# OSO-SCAP-B1-01.net
KiCad netlist of a schematic drawn in EAGLE
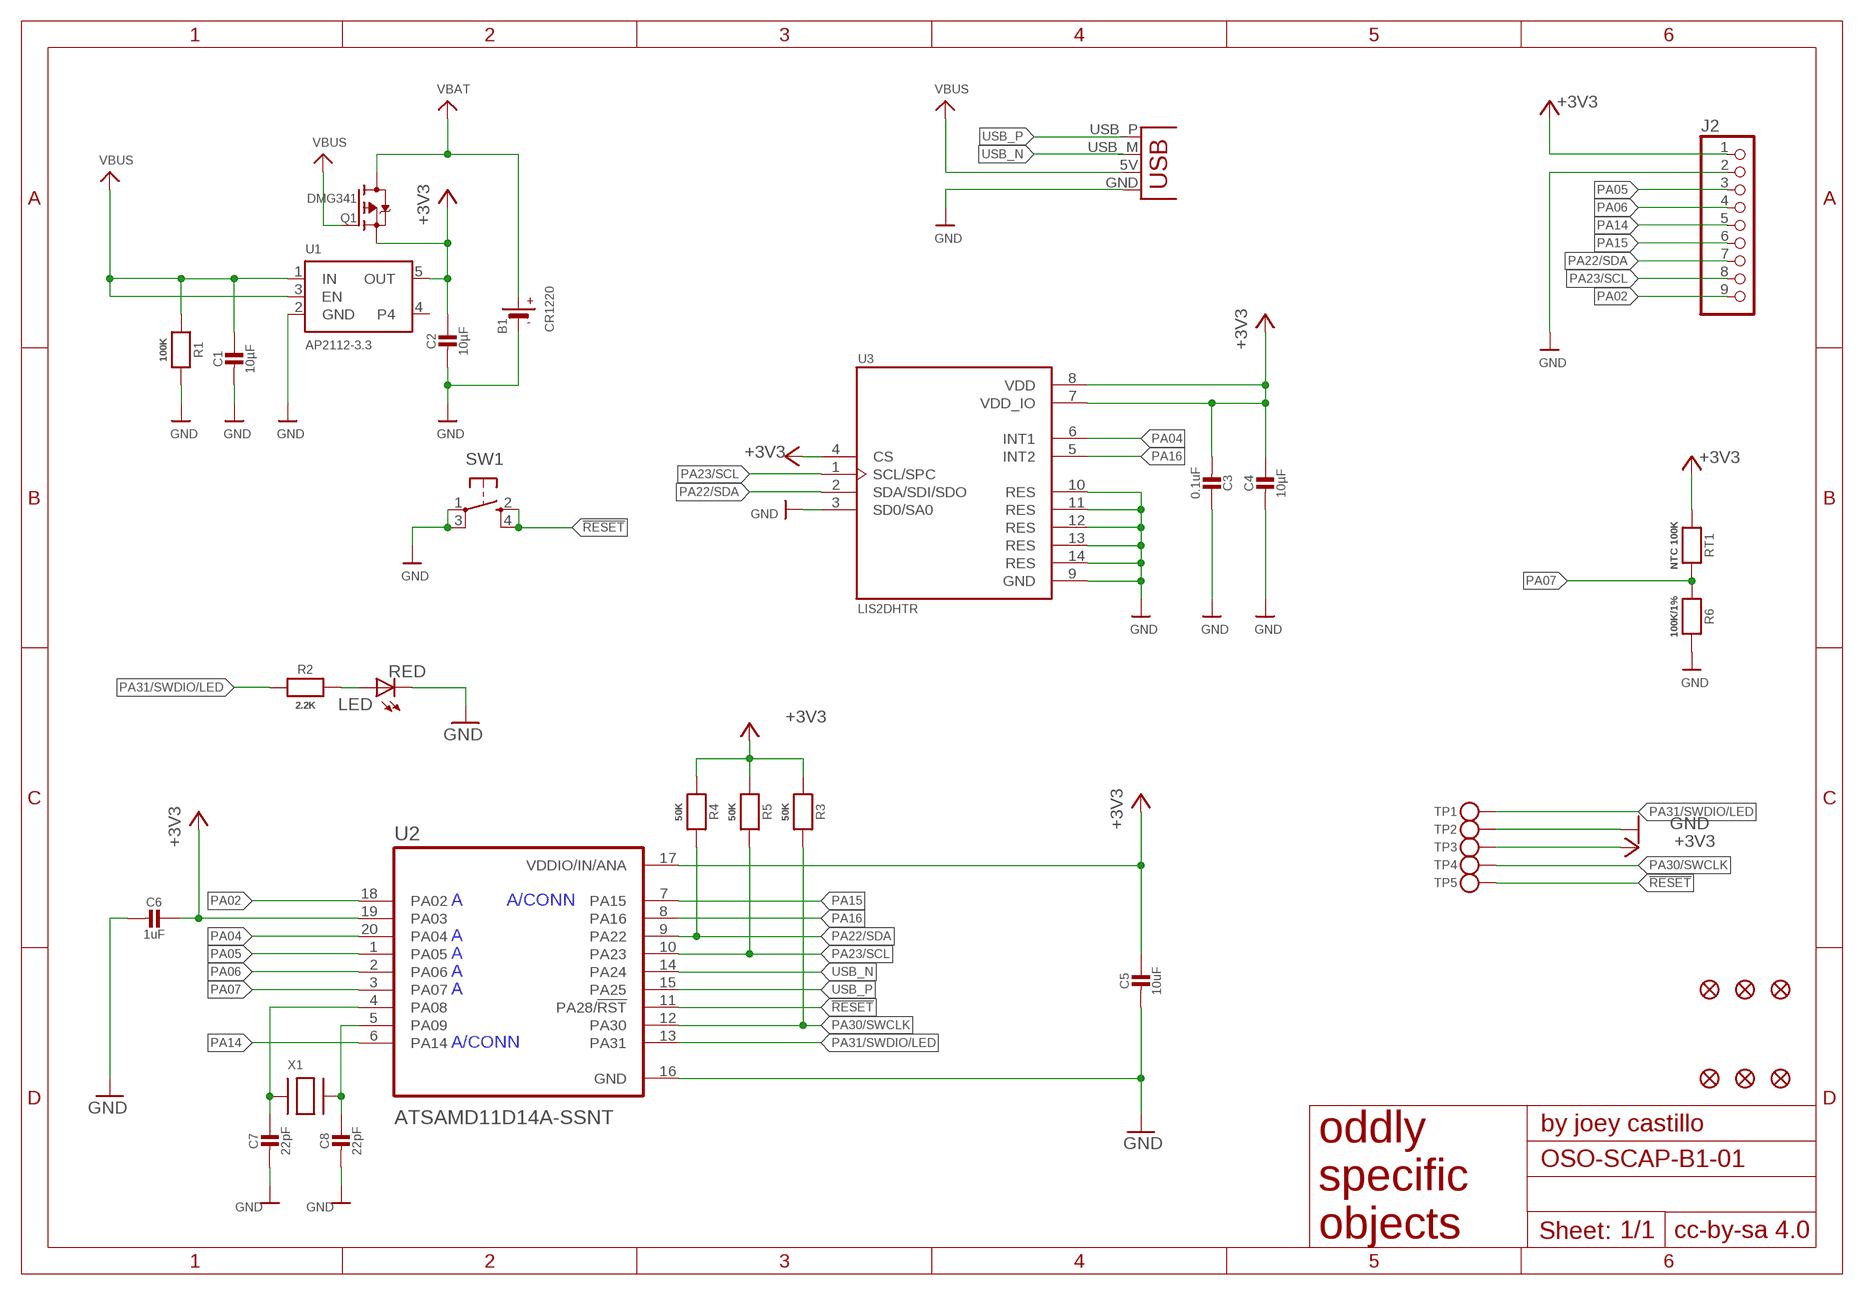
[diagram p0: schematic, sheet 1]

(export (version "E")
  (design (tool "Eeschema 10.0.6"))
  (components
    (comp (ref "B1")
      (value "CR1220")
      (footprint "eagle-import:CR1220")
      (libsource (lib "eagle-import") (part "BATTERYCR1220_SMT"))
    )
    (comp (ref "C1")
      (value "10µF")
      (footprint "eagle-import:0805-NO")
      (libsource (lib "eagle-import") (part "CAP_CERAMIC0805-NOOUTLINE"))
    )
    (comp (ref "C2")
      (value "10µF")
      (footprint "eagle-import:0805-NO")
      (libsource (lib "eagle-import") (part "CAP_CERAMIC0805-NOOUTLINE"))
    )
    (comp (ref "C3")
      (value "0.1uF")
      (footprint "eagle-import:0805-NO")
      (libsource (lib "eagle-import") (part "CAP_CERAMIC0805-NOOUTLINE"))
    )
    (comp (ref "C4")
      (value "10µF")
      (footprint "eagle-import:0805-NO")
      (libsource (lib "eagle-import") (part "CAP_CERAMIC0805-NOOUTLINE"))
    )
    (comp (ref "C5")
      (value "10uF")
      (footprint "eagle-import:0805-NO")
      (libsource (lib "eagle-import") (part "CAP_CERAMIC0805-NOOUTLINE"))
    )
    (comp (ref "C6")
      (value "1uF")
      (footprint "eagle-import:0805-NO")
      (libsource (lib "eagle-import") (part "CAP_CERAMIC0805-NOOUTLINE"))
    )
    (comp (ref "C7")
      (value "22pF")
      (footprint "eagle-import:0805-NO")
      (libsource (lib "eagle-import") (part "CAP_CERAMIC0805-NOOUTLINE"))
    )
    (comp (ref "C8")
      (value "22pF")
      (footprint "eagle-import:0805-NO")
      (libsource (lib "eagle-import") (part "CAP_CERAMIC0805-NOOUTLINE"))
    )
    (comp (ref "FID1")
      (value "FIDUCIAL_1MM")
      (footprint "eagle-import:FIDUCIAL_1MM")
      (libsource (lib "eagle-import") (part "FIDUCIAL_1MM"))
    )
    (comp (ref "FID2")
      (value "FIDUCIAL_1MM")
      (footprint "eagle-import:FIDUCIAL_1MM")
      (libsource (lib "eagle-import") (part "FIDUCIAL_1MM"))
    )
    (comp (ref "FID3")
      (value "FIDUCIAL_1MM")
      (footprint "eagle-import:FIDUCIAL_1MM")
      (libsource (lib "eagle-import") (part "FIDUCIAL_1MM"))
    )
    (comp (ref "FID4")
      (value "FIDUCIAL_1MM")
      (footprint "eagle-import:FIDUCIAL_1MM")
      (libsource (lib "eagle-import") (part "FIDUCIAL_1MM"))
    )
    (comp (ref "FID5")
      (value "FIDUCIAL_1MM")
      (footprint "eagle-import:FIDUCIAL_1MM")
      (libsource (lib "eagle-import") (part "FIDUCIAL_1MM"))
    )
    (comp (ref "FID6")
      (value "FIDUCIAL_1MM")
      (footprint "eagle-import:FIDUCIAL_1MM")
      (libsource (lib "eagle-import") (part "FIDUCIAL_1MM"))
    )
    (comp (ref "J1")
      (value "USBPCB")
      (footprint "eagle-import:USB-A-PCB")
      (libsource (lib "eagle-import") (part "USBPCB"))
    )
    (comp (ref "J2")
      (value "HEADER-1X9_JSTSH")
      (footprint "eagle-import:JST_SH9")
      (libsource (lib "eagle-import") (part "HEADER-1X9_JSTSH"))
    )
    (comp (ref "LED")
      (value "RED")
      (footprint "eagle-import:CHIP-LED0805")
      (libsource (lib "eagle-import") (part "LEDCHIP-LED0805"))
    )
    (comp (ref "Q1")
      (value "DMG341")
      (footprint "eagle-import:SOT23-R")
      (libsource (lib "eagle-import") (part "MOSFET-P"))
    )
    (comp (ref "R1")
      (value "100K")
      (footprint "eagle-import:0805-NO")
      (libsource (lib "eagle-import") (part "RESISTOR0805_NOOUTLINE"))
    )
    (comp (ref "R2")
      (value "2.2K")
      (footprint "eagle-import:0805-NO")
      (libsource (lib "eagle-import") (part "RESISTOR0805_NOOUTLINE"))
    )
    (comp (ref "R3")
      (value "50K")
      (footprint "eagle-import:0805-NO")
      (libsource (lib "eagle-import") (part "RESISTOR0805_NOOUTLINE"))
    )
    (comp (ref "R4")
      (value "50K")
      (footprint "eagle-import:0805-NO")
      (libsource (lib "eagle-import") (part "RESISTOR0805_NOOUTLINE"))
    )
    (comp (ref "R5")
      (value "50K")
      (footprint "eagle-import:0805-NO")
      (libsource (lib "eagle-import") (part "RESISTOR0805_NOOUTLINE"))
    )
    (comp (ref "R6")
      (value "100K/1%")
      (footprint "eagle-import:0805-NO")
      (libsource (lib "eagle-import") (part "RESISTOR0805_NOOUTLINE"))
    )
    (comp (ref "RT1")
      (value "NTC 100K")
      (footprint "eagle-import:0805-NO")
      (libsource (lib "eagle-import") (part "RESISTOR0805_NOOUTLINE"))
    )
    (comp (ref "SW1")
      (value "SPST_TACT-KMR2")
      (footprint "eagle-import:KMR2")
      (libsource (lib "eagle-import") (part "SPST_TACT-KMR2"))
    )
    (comp (ref "TP1")
      (value "TESTPOINTROUND2MMNO")
      (footprint "eagle-import:TESTPOINT_ROUND_2MM_NO")
      (libsource (lib "eagle-import") (part "TESTPOINTROUND2MMNO"))
    )
    (comp (ref "TP2")
      (value "TESTPOINTROUND2MMNO")
      (footprint "eagle-import:TESTPOINT_ROUND_2MM_NO")
      (libsource (lib "eagle-import") (part "TESTPOINTROUND2MMNO"))
    )
    (comp (ref "TP3")
      (value "TESTPOINTROUND2MMNO")
      (footprint "eagle-import:TESTPOINT_ROUND_2MM_NO")
      (libsource (lib "eagle-import") (part "TESTPOINTROUND2MMNO"))
    )
    (comp (ref "TP4")
      (value "TESTPOINTROUND2MMNO")
      (footprint "eagle-import:TESTPOINT_ROUND_2MM_NO")
      (libsource (lib "eagle-import") (part "TESTPOINTROUND2MMNO"))
    )
    (comp (ref "TP5")
      (value "TESTPOINTROUND2MMNO")
      (footprint "eagle-import:TESTPOINT_ROUND_2MM_NO")
      (libsource (lib "eagle-import") (part "TESTPOINTROUND2MMNO"))
    )
    (comp (ref "U1")
      (value "AP2112-3.3")
      (footprint "eagle-import:SOT23-5")
      (libsource (lib "eagle-import") (part "VREG_SOT23-5"))
    )
    (comp (ref "U2")
      (value "ATSAMD11D14A-SSNT")
      (footprint "eagle-import:SOIC127P1030X265-20N")
      (fields (field (name "MF") "Microchip"))
      (libsource (lib "eagle-import") (part "ATSAMD11D14A-SSNT"))
    )
    (comp (ref "U3")
      (value "LIS2DHTR")
      (footprint "eagle-import:PQFN35P200X200X100-14N")
      (fields (field (name "DIGI-KEY_PART_NUMBER") "497-13795-1-ND") (field (name "MF") "STMicroelectronics"))
      (libsource (lib "eagle-import") (part "LIS2DHTR"))
    )
    (comp (ref "X1")
      (value "XTAL-3.2X1.5")
      (footprint "eagle-import:XTAL3215")
      (libsource (lib "eagle-import") (part "XTAL-3.2X1.5"))
    )
  )
  (nets
    (net (code "1") (name "+3V3") (class "Default")
      (node (ref "C2") (pin "1") (pinfunction "1_1") (pintype "passive"))
      (node (ref "C3") (pin "2") (pinfunction "2_2") (pintype "passive"))
      (node (ref "C4") (pin "1") (pinfunction "1_1") (pintype "passive"))
      (node (ref "C5") (pin "1") (pinfunction "1_1") (pintype "passive"))
      (node (ref "C6") (pin "1") (pinfunction "1_1") (pintype "passive"))
      (node (ref "J2") (pin "1") (pinfunction "1_1") (pintype "passive"))
      (node (ref "Q1") (pin "2") (pinfunction "S_2") (pintype "passive"))
      (node (ref "R3") (pin "1") (pinfunction "1_1") (pintype "passive"))
      (node (ref "R4") (pin "1") (pinfunction "1_1") (pintype "passive"))
      (node (ref "R5") (pin "1") (pinfunction "1_1") (pintype "passive"))
      (node (ref "RT1") (pin "1") (pinfunction "1_1") (pintype "passive"))
      (node (ref "TP3") (pin "P$1") (pinfunction "P$1_P$1") (pintype "bidirectional"))
      (node (ref "U1") (pin "5") (pinfunction "OUT_5") (pintype "power_in"))
      (node (ref "U2") (pin "17") (pinfunction "VDDIO/IN/ANA_17") (pintype "power_in"))
      (node (ref "U2") (pin "19") (pinfunction "PA03_19") (pintype "bidirectional"))
      (node (ref "U3") (pin "4") (pinfunction "CS_4") (pintype "input"))
      (node (ref "U3") (pin "7") (pinfunction "VDD_IO_7") (pintype "power_in"))
      (node (ref "U3") (pin "8") (pinfunction "VDD_8") (pintype "power_in"))
    )
    (net (code "2") (name "/~{RESET}") (class "Default")
      (node (ref "SW1") (pin "2") (pinfunction "S_2") (pintype "passive"))
      (node (ref "SW1") (pin "4") (pinfunction "S1_4") (pintype "passive"))
      (node (ref "TP5") (pin "P$1") (pinfunction "P$1_P$1") (pintype "bidirectional"))
      (node (ref "U2") (pin "11") (pinfunction "PA28/~{RST}_11") (pintype "bidirectional"))
    )
    (net (code "3") (name "GND") (class "Default")
      (node (ref "B1") (pin "-") (pinfunction "-_-") (pintype "passive"))
      (node (ref "C1") (pin "2") (pinfunction "2_2") (pintype "passive"))
      (node (ref "C2") (pin "2") (pinfunction "2_2") (pintype "passive"))
      (node (ref "C3") (pin "1") (pinfunction "1_1") (pintype "passive"))
      (node (ref "C4") (pin "2") (pinfunction "2_2") (pintype "passive"))
      (node (ref "C5") (pin "2") (pinfunction "2_2") (pintype "passive"))
      (node (ref "C6") (pin "2") (pinfunction "2_2") (pintype "passive"))
      (node (ref "C7") (pin "2") (pinfunction "2_2") (pintype "passive"))
      (node (ref "C8") (pin "2") (pinfunction "2_2") (pintype "passive"))
      (node (ref "J1") (pin "GND") (pinfunction "GND_GND") (pintype "bidirectional"))
      (node (ref "J2") (pin "2") (pinfunction "2_2") (pintype "passive"))
      (node (ref "LED") (pin "C") (pinfunction "C_C") (pintype "passive"))
      (node (ref "R1") (pin "2") (pinfunction "2_2") (pintype "passive"))
      (node (ref "R6") (pin "2") (pinfunction "2_2") (pintype "passive"))
      (node (ref "SW1") (pin "1") (pinfunction "P_1") (pintype "passive"))
      (node (ref "SW1") (pin "3") (pinfunction "P1_3") (pintype "passive"))
      (node (ref "TP2") (pin "P$1") (pinfunction "P$1_P$1") (pintype "bidirectional"))
      (node (ref "U1") (pin "2") (pinfunction "GND_2") (pintype "power_in"))
      (node (ref "U2") (pin "16") (pinfunction "GND_16") (pintype "power_in"))
      (node (ref "U3") (pin "10") (pinfunction "RES_10") (pintype "power_in"))
      (node (ref "U3") (pin "11") (pinfunction "RES_11") (pintype "power_in"))
      (node (ref "U3") (pin "12") (pinfunction "RES_12") (pintype "power_in"))
      (node (ref "U3") (pin "13") (pinfunction "RES_13") (pintype "power_in"))
      (node (ref "U3") (pin "14") (pinfunction "RES_14") (pintype "power_in"))
      (node (ref "U3") (pin "3") (pinfunction "SD0/SA0_3") (pintype "output"))
      (node (ref "U3") (pin "9") (pinfunction "GND_9") (pintype "power_in"))
    )
    (net (code "4") (name "Net-(LED-PadA)") (class "Default")
      (node (ref "LED") (pin "A") (pinfunction "A_A") (pintype "passive"))
      (node (ref "R2") (pin "2") (pinfunction "2_2") (pintype "passive"))
    )
    (net (code "5") (name "Net-(U2-PA08)") (class "Default")
      (node (ref "C7") (pin "1") (pinfunction "1_1") (pintype "passive"))
      (node (ref "U2") (pin "4") (pinfunction "PA08_4") (pintype "bidirectional"))
      (node (ref "X1") (pin "P$1") (pinfunction "P$1_P$1") (pintype "bidirectional"))
    )
    (net (code "6") (name "Net-(U2-PA09)") (class "Default")
      (node (ref "C8") (pin "1") (pinfunction "1_1") (pintype "passive"))
      (node (ref "U2") (pin "5") (pinfunction "PA09_5") (pintype "bidirectional"))
      (node (ref "X1") (pin "P$2") (pinfunction "P$2_P$2") (pintype "bidirectional"))
    )
    (net (code "7") (name "PA02") (class "Default")
      (node (ref "J2") (pin "9") (pinfunction "9_9") (pintype "passive"))
      (node (ref "U2") (pin "18") (pinfunction "PA02_18") (pintype "bidirectional"))
    )
    (net (code "8") (name "PA04") (class "Default")
      (node (ref "U2") (pin "20") (pinfunction "PA04_20") (pintype "bidirectional"))
      (node (ref "U3") (pin "6") (pinfunction "INT1_6") (pintype "output"))
    )
    (net (code "9") (name "PA05") (class "Default")
      (node (ref "J2") (pin "3") (pinfunction "3_3") (pintype "passive"))
      (node (ref "U2") (pin "1") (pinfunction "PA05_1") (pintype "bidirectional"))
    )
    (net (code "10") (name "PA06") (class "Default")
      (node (ref "J2") (pin "4") (pinfunction "4_4") (pintype "passive"))
      (node (ref "U2") (pin "2") (pinfunction "PA06_2") (pintype "bidirectional"))
    )
    (net (code "11") (name "PA07") (class "Default")
      (node (ref "R6") (pin "1") (pinfunction "1_1") (pintype "passive"))
      (node (ref "RT1") (pin "2") (pinfunction "2_2") (pintype "passive"))
      (node (ref "U2") (pin "3") (pinfunction "PA07_3") (pintype "bidirectional"))
    )
    (net (code "12") (name "PA14") (class "Default")
      (node (ref "J2") (pin "5") (pinfunction "5_5") (pintype "passive"))
      (node (ref "U2") (pin "6") (pinfunction "PA14_6") (pintype "bidirectional"))
    )
    (net (code "13") (name "PA15") (class "Default")
      (node (ref "J2") (pin "6") (pinfunction "6_6") (pintype "passive"))
      (node (ref "U2") (pin "7") (pinfunction "PA15_7") (pintype "bidirectional"))
    )
    (net (code "14") (name "PA16") (class "Default")
      (node (ref "U2") (pin "8") (pinfunction "PA16_8") (pintype "bidirectional"))
      (node (ref "U3") (pin "5") (pinfunction "INT2_5") (pintype "output"))
    )
    (net (code "15") (name "PA22{slash}SDA") (class "Default")
      (node (ref "J2") (pin "7") (pinfunction "7_7") (pintype "passive"))
      (node (ref "R4") (pin "2") (pinfunction "2_2") (pintype "passive"))
      (node (ref "U2") (pin "9") (pinfunction "PA22_9") (pintype "bidirectional"))
      (node (ref "U3") (pin "2") (pinfunction "SDA/SDI/SDO_2") (pintype "bidirectional"))
    )
    (net (code "16") (name "PA23{slash}SCL") (class "Default")
      (node (ref "J2") (pin "8") (pinfunction "8_8") (pintype "passive"))
      (node (ref "R5") (pin "2") (pinfunction "2_2") (pintype "passive"))
      (node (ref "U2") (pin "10") (pinfunction "PA23_10") (pintype "bidirectional"))
      (node (ref "U3") (pin "1") (pinfunction "SCL/SPC_1") (pintype "input"))
    )
    (net (code "17") (name "PA30{slash}SWCLK") (class "Default")
      (node (ref "R3") (pin "2") (pinfunction "2_2") (pintype "passive"))
      (node (ref "TP4") (pin "P$1") (pinfunction "P$1_P$1") (pintype "bidirectional"))
      (node (ref "U2") (pin "12") (pinfunction "PA30_12") (pintype "bidirectional"))
    )
    (net (code "18") (name "PA31{slash}SWDIO{slash}LED") (class "Default")
      (node (ref "R2") (pin "1") (pinfunction "1_1") (pintype "passive"))
      (node (ref "TP1") (pin "P$1") (pinfunction "P$1_P$1") (pintype "bidirectional"))
      (node (ref "U2") (pin "13") (pinfunction "PA31_13") (pintype "bidirectional"))
    )
    (net (code "19") (name "USB_N") (class "Default")
      (node (ref "J1") (pin "USB_M") (pinfunction "D-_USB_M") (pintype "bidirectional"))
      (node (ref "U2") (pin "14") (pinfunction "PA24_14") (pintype "bidirectional"))
    )
    (net (code "20") (name "USB_P") (class "Default")
      (node (ref "J1") (pin "USB_P") (pinfunction "D+_USB_P") (pintype "bidirectional"))
      (node (ref "U2") (pin "15") (pinfunction "PA25_15") (pintype "bidirectional"))
    )
    (net (code "21") (name "VBAT") (class "Default")
      (node (ref "B1") (pin "+$1") (pinfunction "+_+$1") (pintype "passive"))
      (node (ref "B1") (pin "+$2") (pinfunction "+_+$2") (pintype "passive"))
      (node (ref "Q1") (pin "3") (pinfunction "D_3") (pintype "passive"))
    )
    (net (code "22") (name "VBUS") (class "Default")
      (node (ref "C1") (pin "1") (pinfunction "1_1") (pintype "passive"))
      (node (ref "J1") (pin "5V") (pinfunction "VBUS_5V") (pintype "bidirectional"))
      (node (ref "Q1") (pin "1") (pinfunction "G_1") (pintype "passive"))
      (node (ref "R1") (pin "1") (pinfunction "1_1") (pintype "passive"))
      (node (ref "U1") (pin "1") (pinfunction "IN_1") (pintype "power_in"))
      (node (ref "U1") (pin "3") (pinfunction "EN_3") (pintype "input"))
    )
    (net (code "23") (name "unconnected-(U1-P4-Pad4)") (class "Default")
      (node (ref "U1") (pin "4") (pinfunction "P4_4") (pintype "bidirectional"))
    )
  )
)
